# get_it_V4_2.net
KiCad netlist of a schematic drawn in Altium Designer
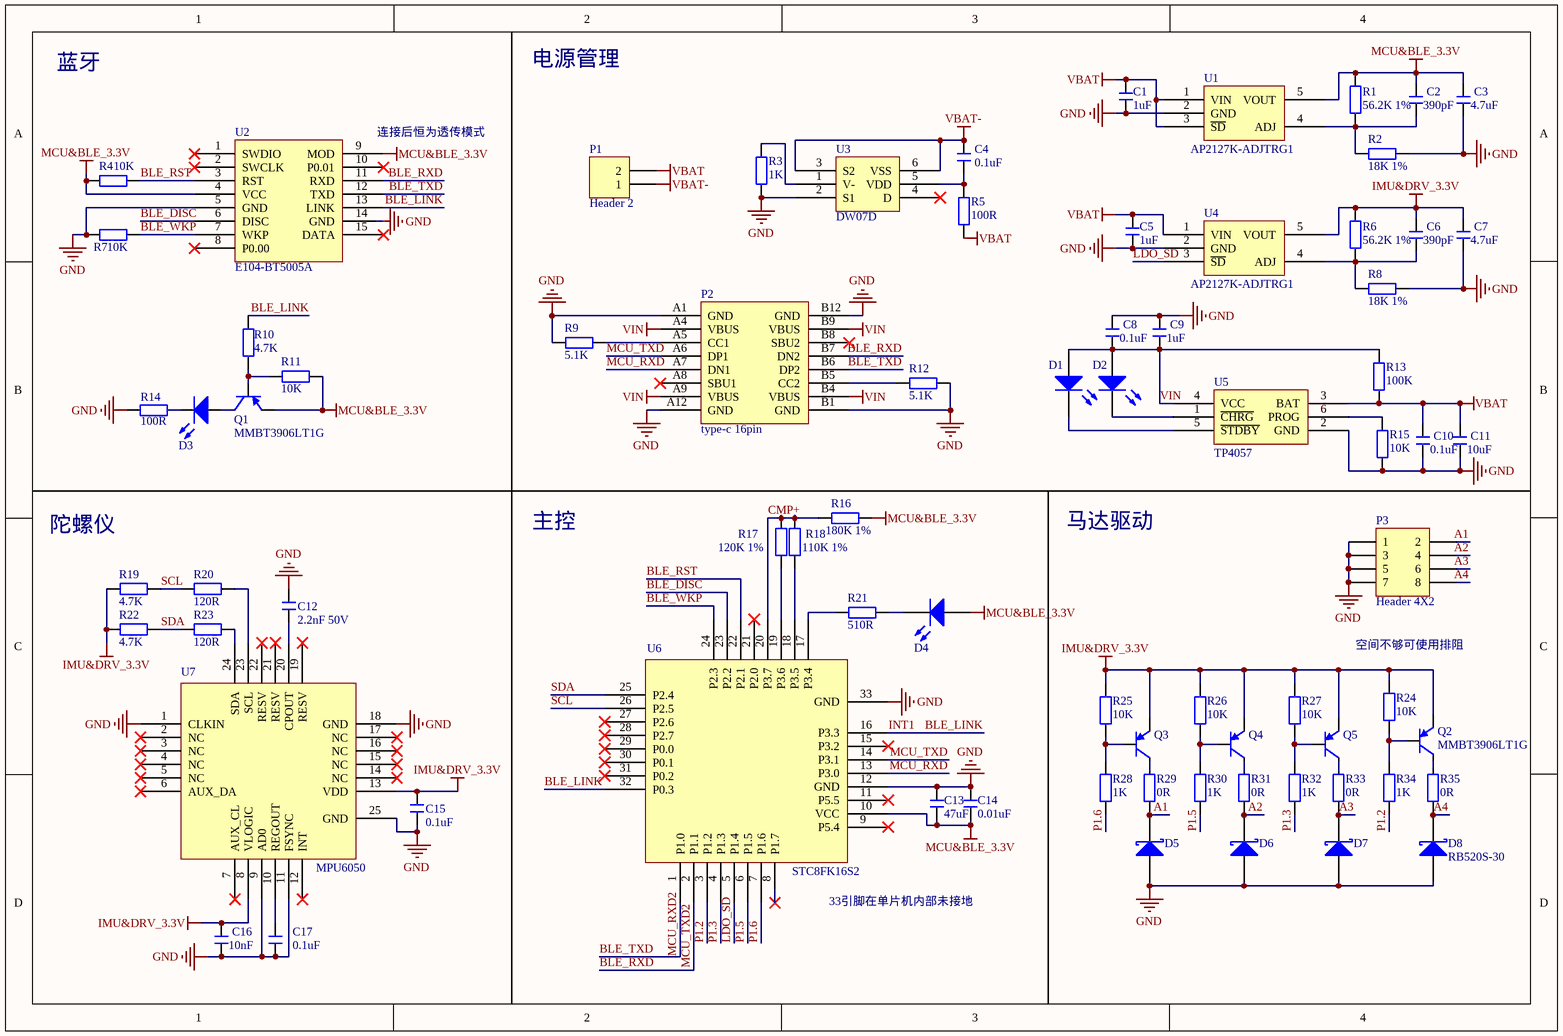
[diagram p0: get it_V4.2.SchDoc]

(export (version "E")
  (design (tool "Eeschema 10.0.6"))
  (components
    (comp (ref "C1")
      (value "1uF")
      (footprint "C 0402_L")
      (description "贴片电容")
      (libsource (lib "altium-import") (part "root_1_C_"))
    )
    (comp (ref "C2")
      (value "390pF")
      (footprint "C 0402_L")
      (description "贴片电容")
      (libsource (lib "altium-import") (part "root_1_C_"))
    )
    (comp (ref "C3")
      (value "4.7uF")
      (footprint "C 0402_L")
      (description "贴片电容")
      (libsource (lib "altium-import") (part "root_1_C_"))
    )
    (comp (ref "C4")
      (value "0.1uF")
      (footprint "C 0402_L")
      (description "贴片电容")
      (libsource (lib "altium-import") (part "root_1_C_"))
    )
    (comp (ref "C5")
      (value "1uF")
      (footprint "C 0402_L")
      (description "贴片电容")
      (libsource (lib "altium-import") (part "root_1_C_"))
    )
    (comp (ref "C6")
      (value "390pF")
      (footprint "C 0402_L")
      (description "贴片电容")
      (libsource (lib "altium-import") (part "root_1_C_"))
    )
    (comp (ref "C7")
      (value "4.7uF")
      (footprint "C 0402_L")
      (description "贴片电容")
      (libsource (lib "altium-import") (part "root_1_C_"))
    )
    (comp (ref "C8")
      (value "0.1uF")
      (footprint "C 0402_L")
      (description "贴片电容")
      (libsource (lib "altium-import") (part "root_1_C_"))
    )
    (comp (ref "C9")
      (value "1uF")
      (footprint "C 0402_L")
      (description "贴片电容")
      (libsource (lib "altium-import") (part "root_1_C_"))
    )
    (comp (ref "C10")
      (value "0.1uF")
      (footprint "C 0402_L")
      (description "贴片电容")
      (libsource (lib "altium-import") (part "root_1_C_"))
    )
    (comp (ref "C11")
      (value "10uF")
      (footprint "C 0402_L")
      (description "贴片电容")
      (libsource (lib "altium-import") (part "root_1_C_"))
    )
    (comp (ref "C12")
      (value "2.2nF 50V")
      (footprint "C 0402_L")
      (description "贴片电容")
      (libsource (lib "altium-import") (part "root_1_C_"))
    )
    (comp (ref "C13")
      (value "47uF")
      (footprint "C 0603_L")
      (description "贴片电容")
      (libsource (lib "altium-import") (part "root_1_C_"))
    )
    (comp (ref "C14")
      (value "0.01uF")
      (footprint "C 0402_L")
      (description "贴片电容")
      (libsource (lib "altium-import") (part "root_1_C_"))
    )
    (comp (ref "C15")
      (value "0.1uF")
      (footprint "C 0402_L")
      (description "贴片电容")
      (libsource (lib "altium-import") (part "root_1_C_"))
    )
    (comp (ref "C16")
      (value "10nF")
      (footprint "C 0402_L")
      (description "贴片电容")
      (libsource (lib "altium-import") (part "root_1_C_"))
    )
    (comp (ref "C17")
      (value "0.1uF")
      (footprint "C 0402_L")
      (description "贴片电容")
      (libsource (lib "altium-import") (part "root_1_C_"))
    )
    (comp (ref "D1")
      (value "LED")
      (footprint "LED_0603")
      (description "发光二极管")
      (libsource (lib "altium-import") (part "root_3_LED_"))
    )
    (comp (ref "D2")
      (value "LED")
      (footprint "LED_0603")
      (description "发光二极管")
      (libsource (lib "altium-import") (part "root_3_LED_"))
    )
    (comp (ref "D3")
      (value "LED")
      (footprint "LED_0603")
      (description "LED GREEN")
      (fields (field (name "PUBLISHER") "Altium Limited"))
      (libsource (lib "Genenal") (part "LED"))
    )
    (comp (ref "D4")
      (value "LED")
      (footprint "LED_0603")
      (description "发光二极管")
      (libsource (lib "altium-import") (part "root_2_LED_"))
    )
    (comp (ref "D5")
      (value "~")
      (footprint "SOD-523")
      (description "肖特基二极管")
      (libsource (lib "altium-import") (part "root_1_SS14_"))
    )
    (comp (ref "D6")
      (value "~")
      (footprint "SOD-523")
      (description "肖特基二极管")
      (libsource (lib "altium-import") (part "root_1_SS14_"))
    )
    (comp (ref "D7")
      (value "~")
      (footprint "SOD-523")
      (description "肖特基二极管")
      (libsource (lib "altium-import") (part "root_1_SS210_"))
    )
    (comp (ref "D8")
      (value "RB520S-30")
      (footprint "SOD-523")
      (description "肖特基二极管")
      (libsource (lib "altium-import") (part "root_1_SS14_"))
    )
    (comp (ref "P1")
      (value "Header 2")
      (footprint "BAT_header")
      (description "Header, 2-Pin")
      (fields (field (name "PUBLISHER") "Altium Limited"))
      (libsource (lib "Miscellaneous Connectors") (part "Header 2"))
    )
    (comp (ref "P2")
      (value "type-c 16pin")
      (footprint "type-c 16pin 沉板母座")
      (libsource (lib "Components") (part "type-c 16pin 沉板母座"))
    )
    (comp (ref "P3")
      (value "Header 4X2")
      (footprint "MOTOR_HEADER")
      (description "Header, 4-Pin, Dual row")
      (fields (field (name "PUBLISHER") "Altium Limited"))
      (libsource (lib "Miscellaneous Connectors") (part "Header 4X2"))
    )
    (comp (ref "Q1")
      (value "MMBT3906LT1G")
      (footprint "SOT23-3L")
      (description "低频放大-PNP型")
      (fields (field (name "版权归属") "封装库来自淘宝 ID：黄晶宝石"))
      (libsource (lib "altium-import") (part "root_3_9012-SMD_"))
    )
    (comp (ref "Q2")
      (value "MMBT3906LT1G")
      (footprint "SOT23-3L")
      (description "低频放大-PNP型")
      (fields (field (name "版权归属") "封装库来自淘宝 ID：黄晶宝石"))
      (libsource (lib "altium-import") (part "root_0_9012-SMD_"))
    )
    (comp (ref "Q3")
      (value "~")
      (footprint "SOT23-3L")
      (description "低频放大-PNP型")
      (fields (field (name "版权归属") "封装库来自淘宝 ID：黄晶宝石"))
      (libsource (lib "altium-import") (part "root_0_9012-SMD_"))
    )
    (comp (ref "Q4")
      (value "~")
      (footprint "SOT23-3L")
      (description "低频放大-PNP型")
      (fields (field (name "版权归属") "封装库来自淘宝 ID：黄晶宝石"))
      (libsource (lib "altium-import") (part "root_0_9012-SMD_"))
    )
    (comp (ref "Q5")
      (value "~")
      (footprint "SOT23-3L")
      (description "低频放大-PNP型")
      (fields (field (name "版权归属") "封装库来自淘宝 ID：黄晶宝石"))
      (libsource (lib "altium-import") (part "root_0_9012-SMD_"))
    )
    (comp (ref "R1")
      (value "56.2K 1%")
      (footprint "R 0402_L")
      (description "贴片电阻")
      (fields (field (name "版权归属") "来自淘宝 ID：黄晶宝石"))
      (libsource (lib "altium-import") (part "root_1_R_"))
    )
    (comp (ref "R2")
      (value "18K 1%")
      (footprint "R 0402_L")
      (description "贴片电阻")
      (fields (field (name "版权归属") "来自淘宝 ID：黄晶宝石"))
      (libsource (lib "altium-import") (part "root_2_R_"))
    )
    (comp (ref "R3")
      (value "1K")
      (footprint "R 0402_L")
      (description "贴片电阻")
      (fields (field (name "版权归属") "来自淘宝 ID：黄晶宝石"))
      (libsource (lib "altium-import") (part "root_1_R_"))
    )
    (comp (ref "R4")
      (value "10K")
      (footprint "R 0402_L")
      (description "贴片电阻")
      (fields (field (name "版权归属") "来自淘宝 ID：黄晶宝石"))
      (libsource (lib "altium-import") (part "root_2_R_"))
    )
    (comp (ref "R5")
      (value "100R")
      (footprint "R 0402_L")
      (description "贴片电阻")
      (fields (field (name "版权归属") "来自淘宝 ID：黄晶宝石"))
      (libsource (lib "altium-import") (part "root_1_R_"))
    )
    (comp (ref "R6")
      (value "56.2K 1%")
      (footprint "R 0402_L")
      (description "贴片电阻")
      (fields (field (name "版权归属") "来自淘宝 ID：黄晶宝石"))
      (libsource (lib "altium-import") (part "root_1_R_"))
    )
    (comp (ref "R7")
      (value "10K")
      (footprint "R 0402_L")
      (description "贴片电阻")
      (fields (field (name "版权归属") "来自淘宝 ID：黄晶宝石"))
      (libsource (lib "altium-import") (part "root_2_R_"))
    )
    (comp (ref "R8")
      (value "18K 1%")
      (footprint "R 0402_L")
      (description "贴片电阻")
      (fields (field (name "版权归属") "来自淘宝 ID：黄晶宝石"))
      (libsource (lib "altium-import") (part "root_2_R_"))
    )
    (comp (ref "R9")
      (value "5.1K")
      (footprint "R 0402_L")
      (description "贴片电阻")
      (fields (field (name "版权归属") "来自淘宝 ID：黄晶宝石"))
      (libsource (lib "0.1 - 电阻-电容-电感") (part "R"))
    )
    (comp (ref "R10")
      (value "4.7K")
      (footprint "R 0402_L")
      (fields (field (name "Comment") "Res") (field (name "PUBLISHER") "Altium Limited"))
      (libsource (lib "") (part "Res_1"))
    )
    (comp (ref "R11")
      (value "10K")
      (footprint "R 0402_L")
      (description "贴片电阻")
      (fields (field (name "版权归属") "来自淘宝 ID：黄晶宝石"))
      (libsource (lib "altium-import") (part "root_2_R_"))
    )
    (comp (ref "R12")
      (value "5.1K")
      (footprint "R 0402_L")
      (description "贴片电阻")
      (fields (field (name "版权归属") "来自淘宝 ID：黄晶宝石"))
      (libsource (lib "0.1 - 电阻-电容-电感") (part "R"))
    )
    (comp (ref "R13")
      (value "100K")
      (footprint "R 0402_L")
      (description "贴片电阻")
      (fields (field (name "版权归属") "来自淘宝 ID：黄晶宝石"))
      (libsource (lib "altium-import") (part "root_1_R_"))
    )
    (comp (ref "R14")
      (value "100R")
      (footprint "R 0402_L")
      (fields (field (name "Comment") "Res") (field (name "PUBLISHER") "Altium Limited"))
      (libsource (lib "Genenal") (part "Res"))
    )
    (comp (ref "R15")
      (value "10K")
      (footprint "R 0402_L")
      (description "贴片电阻")
      (fields (field (name "版权归属") "来自淘宝 ID：黄晶宝石"))
      (libsource (lib "altium-import") (part "root_1_R_"))
    )
    (comp (ref "R16")
      (value "180K 1%")
      (footprint "R 0402_L")
      (description "贴片电阻")
      (fields (field (name "版权归属") "来自淘宝 ID：黄晶宝石"))
      (libsource (lib "altium-import") (part "root_2_R_"))
    )
    (comp (ref "R17")
      (value "120K 1%")
      (footprint "R 0402_L")
      (description "贴片电阻")
      (fields (field (name "版权归属") "来自淘宝 ID：黄晶宝石"))
      (libsource (lib "altium-import") (part "root_3_R_"))
    )
    (comp (ref "R18")
      (value "110K 1%")
      (footprint "R 0402_L")
      (description "贴片电阻")
      (fields (field (name "版权归属") "来自淘宝 ID：黄晶宝石"))
      (libsource (lib "altium-import") (part "root_3_R_"))
    )
    (comp (ref "R19")
      (value "4.7K")
      (footprint "R 0402_L")
      (description "贴片电阻")
      (fields (field (name "版权归属") "来自淘宝 ID：黄晶宝石"))
      (libsource (lib "altium-import") (part "root_0_R_"))
    )
    (comp (ref "R20")
      (value "120R")
      (footprint "R 0402_L")
      (description "贴片电阻")
      (fields (field (name "版权归属") "来自淘宝 ID：黄晶宝石"))
      (libsource (lib "altium-import") (part "root_0_R_"))
    )
    (comp (ref "R21")
      (value "510R")
      (footprint "R 0402_L")
      (description "贴片电阻")
      (fields (field (name "版权归属") "来自淘宝 ID：黄晶宝石"))
      (libsource (lib "altium-import") (part "root_2_R_"))
    )
    (comp (ref "R22")
      (value "4.7K")
      (footprint "R 0402_L")
      (description "贴片电阻")
      (fields (field (name "版权归属") "来自淘宝 ID：黄晶宝石"))
      (libsource (lib "altium-import") (part "root_0_R_"))
    )
    (comp (ref "R23")
      (value "120R")
      (footprint "R 0402_L")
      (description "贴片电阻")
      (fields (field (name "版权归属") "来自淘宝 ID：黄晶宝石"))
      (libsource (lib "altium-import") (part "root_0_R_"))
    )
    (comp (ref "R24")
      (value "10K")
      (footprint "R 0402_L")
      (description "贴片电阻")
      (fields (field (name "版权归属") "来自淘宝 ID：黄晶宝石"))
      (libsource (lib "altium-import") (part "root_1_R_"))
    )
    (comp (ref "R25")
      (value "10K")
      (footprint "R 0402_L")
      (description "贴片电阻")
      (fields (field (name "版权归属") "来自淘宝 ID：黄晶宝石"))
      (libsource (lib "altium-import") (part "root_1_R_"))
    )
    (comp (ref "R26")
      (value "10K")
      (footprint "R 0402_L")
      (description "贴片电阻")
      (fields (field (name "版权归属") "来自淘宝 ID：黄晶宝石"))
      (libsource (lib "altium-import") (part "root_1_R_"))
    )
    (comp (ref "R27")
      (value "10K")
      (footprint "R 0402_L")
      (description "贴片电阻")
      (fields (field (name "版权归属") "来自淘宝 ID：黄晶宝石"))
      (libsource (lib "altium-import") (part "root_1_R_"))
    )
    (comp (ref "R28")
      (value "1K")
      (footprint "R 0402_L")
      (description "贴片电阻")
      (fields (field (name "版权归属") "来自淘宝 ID：黄晶宝石"))
      (libsource (lib "altium-import") (part "root_1_R_"))
    )
    (comp (ref "R29")
      (value "0R")
      (footprint "R 0402_L")
      (description "贴片电阻")
      (fields (field (name "版权归属") "来自淘宝 ID：黄晶宝石"))
      (libsource (lib "altium-import") (part "root_1_R_"))
    )
    (comp (ref "R30")
      (value "1K")
      (footprint "R 0402_L")
      (description "贴片电阻")
      (fields (field (name "版权归属") "来自淘宝 ID：黄晶宝石"))
      (libsource (lib "altium-import") (part "root_1_R_"))
    )
    (comp (ref "R31")
      (value "0R")
      (footprint "R 0402_L")
      (description "贴片电阻")
      (fields (field (name "版权归属") "来自淘宝 ID：黄晶宝石"))
      (libsource (lib "altium-import") (part "root_1_R_"))
    )
    (comp (ref "R32")
      (value "1K")
      (footprint "R 0402_L")
      (description "贴片电阻")
      (fields (field (name "版权归属") "来自淘宝 ID：黄晶宝石"))
      (libsource (lib "altium-import") (part "root_1_R_"))
    )
    (comp (ref "R33")
      (value "0R")
      (footprint "R 0402_L")
      (description "贴片电阻")
      (fields (field (name "版权归属") "来自淘宝 ID：黄晶宝石"))
      (libsource (lib "altium-import") (part "root_1_R_"))
    )
    (comp (ref "R34")
      (value "1K")
      (footprint "R 0402_L")
      (description "贴片电阻")
      (fields (field (name "版权归属") "来自淘宝 ID：黄晶宝石"))
      (libsource (lib "altium-import") (part "root_1_R_"))
    )
    (comp (ref "R35")
      (value "0R")
      (footprint "R 0402_L")
      (description "贴片电阻")
      (fields (field (name "版权归属") "来自淘宝 ID：黄晶宝石"))
      (libsource (lib "altium-import") (part "root_1_R_"))
    )
    (comp (ref "U1")
      (value "AP2127K-ADJTRG1")
      (footprint "SOT-23-5")
      (libsource (lib "Components") (part "AP2127K-ADJTRG1"))
    )
    (comp (ref "U2")
      (value "E104-BT5005A")
      (footprint "E104-BT5005A")
      (libsource (lib "Components") (part "E104-BT5005A"))
    )
    (comp (ref "U3") (value "DW07D") (footprint "SOT-23-6") (libsource (lib "Components") (part "DW06D")))
    (comp (ref "U4")
      (value "AP2127K-ADJTRG1")
      (footprint "SOT-23-5")
      (libsource (lib "Components") (part "AP2127K-ADJTRG1"))
    )
    (comp (ref "U5") (value "TP4057") (footprint "SOT-23-6") (libsource (lib "Components") (part "TP4057")))
    (comp (ref "U6")
      (value "STC8FK16S2")
      (footprint "QFN40P400X400X75_HS-33N")
      (libsource (lib "Components") (part "STC8FK16S2(QFN32)"))
    )
    (comp (ref "U7")
      (value "MPU6050")
      (footprint "QFN50P400X400X90_HS-25N")
      (libsource (lib "Components") (part "MPU6050"))
    )
  )
  (nets
    (net (code "1") (name "/A1") (class "Default")
      (node (ref "D5") (pin "2") (pinfunction "K_2") (pintype "passive"))
      (node (ref "P3") (pin "2") (pinfunction "2_2") (pintype "passive"))
      (node (ref "R29") (pin "1") (pinfunction "1_1") (pintype "passive"))
    )
    (net (code "2") (name "/A2") (class "Default")
      (node (ref "D6") (pin "2") (pinfunction "K_2") (pintype "passive"))
      (node (ref "P3") (pin "4") (pinfunction "4_4") (pintype "passive"))
      (node (ref "R31") (pin "1") (pinfunction "1_1") (pintype "passive"))
    )
    (net (code "3") (name "/A3") (class "Default")
      (node (ref "D7") (pin "2") (pinfunction "K_2") (pintype "passive"))
      (node (ref "P3") (pin "6") (pinfunction "6_6") (pintype "passive"))
      (node (ref "R33") (pin "1") (pinfunction "1_1") (pintype "passive"))
    )
    (net (code "4") (name "/A4") (class "Default")
      (node (ref "D8") (pin "2") (pinfunction "K_2") (pintype "passive"))
      (node (ref "P3") (pin "8") (pinfunction "8_8") (pintype "passive"))
      (node (ref "R35") (pin "1") (pinfunction "1_1") (pintype "passive"))
    )
    (net (code "5") (name "/BLE_DISC") (class "Default")
      (node (ref "U2") (pin "6") (pinfunction "DISC_6") (pintype "passive"))
      (node (ref "U6") (pin "23") (pinfunction "P2.2_23") (pintype "passive"))
    )
    (net (code "6") (name "/BLE_LINK") (class "Default")
      (node (ref "R10") (pin "2") (pinfunction "2_2") (pintype "passive"))
      (node (ref "U2") (pin "13") (pinfunction "LINK_13") (pintype "passive"))
      (node (ref "U6") (pin "16") (pinfunction "P3.3_16") (pintype "passive"))
      (node (ref "U6") (pin "32") (pinfunction "P0.3_32") (pintype "passive"))
    )
    (net (code "7") (name "/BLE_RST") (class "Default")
      (node (ref "R4") (pin "1") (pinfunction "1_1") (pintype "passive"))
      (node (ref "U2") (pin "3") (pinfunction "RST_3") (pintype "passive"))
      (node (ref "U6") (pin "22") (pinfunction "P2.1_22") (pintype "passive"))
    )
    (net (code "8") (name "/BLE_RXD") (class "Default")
      (node (ref "P2") (pin "B7") (pinfunction "DN2_B7") (pintype "passive"))
      (node (ref "U2") (pin "11") (pinfunction "RXD_11") (pintype "passive"))
      (node (ref "U6") (pin "2") (pinfunction "P1.1_2") (pintype "passive"))
    )
    (net (code "9") (name "/BLE_TXD") (class "Default")
      (node (ref "P2") (pin "B6") (pinfunction "DP2_B6") (pintype "passive"))
      (node (ref "U2") (pin "12") (pinfunction "TXD_12") (pintype "passive"))
      (node (ref "U6") (pin "1") (pinfunction "P1.0_1") (pintype "passive"))
    )
    (net (code "10") (name "/BLE_WKP") (class "Default")
      (node (ref "R7") (pin "1") (pinfunction "1_1") (pintype "passive"))
      (node (ref "U2") (pin "7") (pinfunction "WKP_7") (pintype "passive"))
      (node (ref "U6") (pin "24") (pinfunction "P2.3_24") (pintype "passive"))
    )
    (net (code "11") (name "/CMP+") (class "Default")
      (node (ref "R16") (pin "2") (pinfunction "2_2") (pintype "passive"))
      (node (ref "R17") (pin "1") (pinfunction "1_1") (pintype "passive"))
      (node (ref "R18") (pin "1") (pinfunction "1_1") (pintype "passive"))
      (node (ref "U6") (pin "20") (pinfunction "P3.7_20") (pintype "passive"))
    )
    (net (code "12") (name "/LDO_SD") (class "Default")
      (node (ref "U4") (pin "3") (pinfunction "~{SD}_3") (pintype "passive"))
      (node (ref "U6") (pin "5") (pinfunction "P1.4_5") (pintype "passive"))
    )
    (net (code "13") (name "/MCU_RXD") (class "Default")
      (node (ref "P2") (pin "A7") (pinfunction "DN1_A7") (pintype "passive"))
      (node (ref "U6") (pin "13") (pinfunction "P3.0_13") (pintype "passive"))
    )
    (net (code "14") (name "/MCU_TXD") (class "Default")
      (node (ref "P2") (pin "A6") (pinfunction "DP1_A6") (pintype "passive"))
      (node (ref "U6") (pin "14") (pinfunction "P3.1_14") (pintype "passive"))
    )
    (net (code "15") (name "/P1.2") (class "Default")
      (node (ref "R34") (pin "1") (pinfunction "1_1") (pintype "passive"))
      (node (ref "U6") (pin "3") (pinfunction "P1.2_3") (pintype "passive"))
    )
    (net (code "16") (name "/P1.3") (class "Default")
      (node (ref "R32") (pin "1") (pinfunction "1_1") (pintype "passive"))
      (node (ref "U6") (pin "4") (pinfunction "P1.3_4") (pintype "passive"))
    )
    (net (code "17") (name "/P1.5") (class "Default")
      (node (ref "R30") (pin "1") (pinfunction "1_1") (pintype "passive"))
      (node (ref "U6") (pin "6") (pinfunction "P1.5_6") (pintype "passive"))
    )
    (net (code "18") (name "/P1.6") (class "Default")
      (node (ref "R28") (pin "1") (pinfunction "1_1") (pintype "passive"))
      (node (ref "U6") (pin "7") (pinfunction "P1.6_7") (pintype "passive"))
    )
    (net (code "19") (name "/SCL") (class "Default")
      (node (ref "R19") (pin "2") (pinfunction "2_2") (pintype "passive"))
      (node (ref "R20") (pin "1") (pinfunction "1_1") (pintype "passive"))
      (node (ref "U6") (pin "26") (pinfunction "P2.5_26") (pintype "passive"))
    )
    (net (code "20") (name "/SDA") (class "Default")
      (node (ref "R22") (pin "2") (pinfunction "2_2") (pintype "passive"))
      (node (ref "R23") (pin "1") (pinfunction "1_1") (pintype "passive"))
      (node (ref "U6") (pin "25") (pinfunction "P2.4_25") (pintype "passive"))
    )
    (net (code "21") (name "GND") (class "Default")
      (node (ref "C1") (pin "1") (pinfunction "1_1") (pintype "passive"))
      (node (ref "C10") (pin "1") (pinfunction "1_1") (pintype "passive"))
      (node (ref "C11") (pin "1") (pinfunction "1_1") (pintype "passive"))
      (node (ref "C12") (pin "2") (pinfunction "2_2") (pintype "passive"))
      (node (ref "C13") (pin "2") (pinfunction "2_2") (pintype "passive"))
      (node (ref "C14") (pin "2") (pinfunction "2_2") (pintype "passive"))
      (node (ref "C15") (pin "1") (pinfunction "1_1") (pintype "passive"))
      (node (ref "C16") (pin "1") (pinfunction "1_1") (pintype "passive"))
      (node (ref "C17") (pin "1") (pinfunction "1_1") (pintype "passive"))
      (node (ref "C3") (pin "1") (pinfunction "1_1") (pintype "passive"))
      (node (ref "C5") (pin "1") (pinfunction "1_1") (pintype "passive"))
      (node (ref "C7") (pin "1") (pinfunction "1_1") (pintype "passive"))
      (node (ref "C8") (pin "2") (pinfunction "2_2") (pintype "passive"))
      (node (ref "C9") (pin "2") (pinfunction "2_2") (pintype "passive"))
      (node (ref "D5") (pin "1") (pinfunction "A_1") (pintype "passive"))
      (node (ref "D6") (pin "1") (pinfunction "A_1") (pintype "passive"))
      (node (ref "D7") (pin "1") (pinfunction "A_1") (pintype "passive"))
      (node (ref "D8") (pin "1") (pinfunction "A_1") (pintype "passive"))
      (node (ref "P2") (pin "A1") (pinfunction "GND_A1") (pintype "passive"))
      (node (ref "P2") (pin "A12") (pinfunction "GND_A12") (pintype "passive"))
      (node (ref "P2") (pin "B1") (pinfunction "GND_B1") (pintype "passive"))
      (node (ref "P2") (pin "B12") (pinfunction "GND_B12") (pintype "passive"))
      (node (ref "P3") (pin "1") (pinfunction "1_1") (pintype "passive"))
      (node (ref "P3") (pin "3") (pinfunction "3_3") (pintype "passive"))
      (node (ref "P3") (pin "5") (pinfunction "5_5") (pintype "passive"))
      (node (ref "P3") (pin "7") (pinfunction "7_7") (pintype "passive"))
      (node (ref "R12") (pin "2") (pinfunction "2_2") (pintype "passive"))
      (node (ref "R14") (pin "2") (pinfunction "2_2") (pintype "passive"))
      (node (ref "R15") (pin "1") (pinfunction "1_1") (pintype "passive"))
      (node (ref "R2") (pin "1") (pinfunction "1_1") (pintype "passive"))
      (node (ref "R3") (pin "1") (pinfunction "1_1") (pintype "passive"))
      (node (ref "R7") (pin "2") (pinfunction "2_2") (pintype "passive"))
      (node (ref "R8") (pin "1") (pinfunction "1_1") (pintype "passive"))
      (node (ref "R9") (pin "1") (pinfunction "1_1") (pintype "passive"))
      (node (ref "U1") (pin "2") (pinfunction "GND_2") (pintype "passive"))
      (node (ref "U2") (pin "14") (pinfunction "GND_14") (pintype "passive"))
      (node (ref "U2") (pin "5") (pinfunction "GND_5") (pintype "passive"))
      (node (ref "U3") (pin "2") (pinfunction "S1_2") (pintype "passive"))
      (node (ref "U4") (pin "2") (pinfunction "GND_2") (pintype "passive"))
      (node (ref "U5") (pin "2") (pinfunction "GND_2") (pintype "passive"))
      (node (ref "U6") (pin "12") (pinfunction "GND_12") (pintype "passive"))
      (node (ref "U6") (pin "33") (pinfunction "GND_33") (pintype "passive"))
      (node (ref "U7") (pin "1") (pinfunction "CLKIN_1") (pintype "passive"))
      (node (ref "U7") (pin "11") (pinfunction "FSYNC_11") (pintype "passive"))
      (node (ref "U7") (pin "18") (pinfunction "GND_18") (pintype "passive"))
      (node (ref "U7") (pin "25") (pinfunction "GND_25") (pintype "passive"))
      (node (ref "U7") (pin "9") (pinfunction "AD0_9") (pintype "passive"))
    )
    (net (code "22") (name "IMU&DRV_3.3V") (class "Default")
      (node (ref "C15") (pin "2") (pinfunction "2_2") (pintype "passive"))
      (node (ref "C16") (pin "2") (pinfunction "2_2") (pintype "passive"))
      (node (ref "C6") (pin "2") (pinfunction "2_2") (pintype "passive"))
      (node (ref "C7") (pin "2") (pinfunction "2_2") (pintype "passive"))
      (node (ref "Q2") (pin "2") (pinfunction "E_2") (pintype "passive"))
      (node (ref "Q3") (pin "2") (pinfunction "E_2") (pintype "passive"))
      (node (ref "Q4") (pin "2") (pinfunction "E_2") (pintype "passive"))
      (node (ref "Q5") (pin "2") (pinfunction "E_2") (pintype "passive"))
      (node (ref "R19") (pin "1") (pinfunction "1_1") (pintype "passive"))
      (node (ref "R22") (pin "1") (pinfunction "1_1") (pintype "passive"))
      (node (ref "R24") (pin "2") (pinfunction "2_2") (pintype "passive"))
      (node (ref "R25") (pin "2") (pinfunction "2_2") (pintype "passive"))
      (node (ref "R26") (pin "2") (pinfunction "2_2") (pintype "passive"))
      (node (ref "R27") (pin "2") (pinfunction "2_2") (pintype "passive"))
      (node (ref "R6") (pin "2") (pinfunction "2_2") (pintype "passive"))
      (node (ref "U4") (pin "5") (pinfunction "VOUT_5") (pintype "passive"))
      (node (ref "U7") (pin "13") (pinfunction "VDD_13") (pintype "passive"))
      (node (ref "U7") (pin "8") (pinfunction "VLOGIC_8") (pintype "passive"))
    )
    (net (code "23") (name "MCU&BLE_3.3V") (class "Default")
      (node (ref "C13") (pin "1") (pinfunction "1_1") (pintype "passive"))
      (node (ref "C14") (pin "1") (pinfunction "1_1") (pintype "passive"))
      (node (ref "C2") (pin "2") (pinfunction "2_2") (pintype "passive"))
      (node (ref "C3") (pin "2") (pinfunction "2_2") (pintype "passive"))
      (node (ref "D4") (pin "1") (pinfunction "A_1") (pintype "passive"))
      (node (ref "Q1") (pin "2") (pinfunction "E_2") (pintype "passive"))
      (node (ref "R1") (pin "2") (pinfunction "2_2") (pintype "passive"))
      (node (ref "R11") (pin "1") (pinfunction "1_1") (pintype "passive"))
      (node (ref "R16") (pin "1") (pinfunction "1_1") (pintype "passive"))
      (node (ref "R4") (pin "2") (pinfunction "2_2") (pintype "passive"))
      (node (ref "U1") (pin "5") (pinfunction "VOUT_5") (pintype "passive"))
      (node (ref "U2") (pin "4") (pinfunction "VCC_4") (pintype "passive"))
      (node (ref "U2") (pin "9") (pinfunction "MOD_9") (pintype "passive"))
      (node (ref "U6") (pin "10") (pinfunction "VCC_10") (pintype "passive"))
    )
    (net (code "24") (name "Net-(D1-K)") (class "Default")
      (node (ref "D1") (pin "2") (pinfunction "K_2") (pintype "passive"))
      (node (ref "U5") (pin "5") (pinfunction "~{STDBY}_5") (pintype "passive"))
    )
    (net (code "25") (name "Net-(D2-K)") (class "Default")
      (node (ref "D2") (pin "2") (pinfunction "K_2") (pintype "passive"))
      (node (ref "U5") (pin "1") (pinfunction "~{CHRG}_1") (pintype "passive"))
    )
    (net (code "26") (name "Net-(D3-A)") (class "Default")
      (node (ref "D3") (pin "1") (pinfunction "A_1") (pintype "passive"))
      (node (ref "Q1") (pin "3") (pinfunction "C_3") (pintype "passive"))
    )
    (net (code "27") (name "Net-(D3-K)") (class "Default")
      (node (ref "D3") (pin "2") (pinfunction "K_2") (pintype "passive"))
      (node (ref "R14") (pin "1") (pinfunction "1_1") (pintype "passive"))
    )
    (net (code "28") (name "Net-(D4-K)") (class "Default")
      (node (ref "D4") (pin "2") (pinfunction "K_2") (pintype "passive"))
      (node (ref "R21") (pin "1") (pinfunction "1_1") (pintype "passive"))
    )
    (net (code "29") (name "Net-(P2-CC1)") (class "Default")
      (node (ref "P2") (pin "A5") (pinfunction "CC1_A5") (pintype "passive"))
      (node (ref "R9") (pin "2") (pinfunction "2_2") (pintype "passive"))
    )
    (net (code "30") (name "Net-(P2-CC2)") (class "Default")
      (node (ref "P2") (pin "B5") (pinfunction "CC2_B5") (pintype "passive"))
      (node (ref "R12") (pin "1") (pinfunction "1_1") (pintype "passive"))
    )
    (net (code "31") (name "Net-(Q1-B)") (class "Default")
      (node (ref "Q1") (pin "1") (pinfunction "B_1") (pintype "passive"))
      (node (ref "R10") (pin "1") (pinfunction "1_1") (pintype "passive"))
      (node (ref "R11") (pin "2") (pinfunction "2_2") (pintype "passive"))
    )
    (net (code "32") (name "Net-(Q2-B)") (class "Default")
      (node (ref "Q2") (pin "1") (pinfunction "B_1") (pintype "passive"))
      (node (ref "R24") (pin "1") (pinfunction "1_1") (pintype "passive"))
      (node (ref "R34") (pin "2") (pinfunction "2_2") (pintype "passive"))
    )
    (net (code "33") (name "Net-(Q2-C)") (class "Default")
      (node (ref "Q2") (pin "3") (pinfunction "C_3") (pintype "passive"))
      (node (ref "R35") (pin "2") (pinfunction "2_2") (pintype "passive"))
    )
    (net (code "34") (name "Net-(Q3-B)") (class "Default")
      (node (ref "Q3") (pin "1") (pinfunction "B_1") (pintype "passive"))
      (node (ref "R25") (pin "1") (pinfunction "1_1") (pintype "passive"))
      (node (ref "R28") (pin "2") (pinfunction "2_2") (pintype "passive"))
    )
    (net (code "35") (name "Net-(Q3-C)") (class "Default")
      (node (ref "Q3") (pin "3") (pinfunction "C_3") (pintype "passive"))
      (node (ref "R29") (pin "2") (pinfunction "2_2") (pintype "passive"))
    )
    (net (code "36") (name "Net-(Q4-B)") (class "Default")
      (node (ref "Q4") (pin "1") (pinfunction "B_1") (pintype "passive"))
      (node (ref "R26") (pin "1") (pinfunction "1_1") (pintype "passive"))
      (node (ref "R30") (pin "2") (pinfunction "2_2") (pintype "passive"))
    )
    (net (code "37") (name "Net-(Q4-C)") (class "Default")
      (node (ref "Q4") (pin "3") (pinfunction "C_3") (pintype "passive"))
      (node (ref "R31") (pin "2") (pinfunction "2_2") (pintype "passive"))
    )
    (net (code "38") (name "Net-(Q5-B)") (class "Default")
      (node (ref "Q5") (pin "1") (pinfunction "B_1") (pintype "passive"))
      (node (ref "R27") (pin "1") (pinfunction "1_1") (pintype "passive"))
      (node (ref "R32") (pin "2") (pinfunction "2_2") (pintype "passive"))
    )
    (net (code "39") (name "Net-(Q5-C)") (class "Default")
      (node (ref "Q5") (pin "3") (pinfunction "C_3") (pintype "passive"))
      (node (ref "R33") (pin "2") (pinfunction "2_2") (pintype "passive"))
    )
    (net (code "40") (name "Net-(U1-ADJ)") (class "Default")
      (node (ref "C2") (pin "1") (pinfunction "1_1") (pintype "passive"))
      (node (ref "R1") (pin "1") (pinfunction "1_1") (pintype "passive"))
      (node (ref "R2") (pin "2") (pinfunction "2_2") (pintype "passive"))
      (node (ref "U1") (pin "4") (pinfunction "ADJ_4") (pintype "passive"))
    )
    (net (code "41") (name "Net-(U3-V-)") (class "Default")
      (node (ref "R3") (pin "2") (pinfunction "2_2") (pintype "passive"))
      (node (ref "U3") (pin "1") (pinfunction "V-_1") (pintype "passive"))
    )
    (net (code "42") (name "Net-(U3-VDD)") (class "Default")
      (node (ref "C4") (pin "1") (pinfunction "1_1") (pintype "passive"))
      (node (ref "R5") (pin "2") (pinfunction "2_2") (pintype "passive"))
      (node (ref "U3") (pin "5") (pinfunction "VDD_5") (pintype "passive"))
    )
    (net (code "43") (name "Net-(U4-ADJ)") (class "Default")
      (node (ref "C6") (pin "1") (pinfunction "1_1") (pintype "passive"))
      (node (ref "R6") (pin "1") (pinfunction "1_1") (pintype "passive"))
      (node (ref "R8") (pin "2") (pinfunction "2_2") (pintype "passive"))
      (node (ref "U4") (pin "4") (pinfunction "ADJ_4") (pintype "passive"))
    )
    (net (code "44") (name "Net-(U5-PROG)") (class "Default")
      (node (ref "R15") (pin "2") (pinfunction "2_2") (pintype "passive"))
      (node (ref "U5") (pin "6") (pinfunction "PROG_6") (pintype "passive"))
    )
    (net (code "45") (name "Net-(U6-P3.4)") (class "Default")
      (node (ref "R21") (pin "2") (pinfunction "2_2") (pintype "passive"))
      (node (ref "U6") (pin "17") (pinfunction "P3.4_17") (pintype "passive"))
    )
    (net (code "46") (name "Net-(U6-P3.5)") (class "Default")
      (node (ref "R18") (pin "2") (pinfunction "2_2") (pintype "passive"))
      (node (ref "U6") (pin "18") (pinfunction "P3.5_18") (pintype "passive"))
    )
    (net (code "47") (name "Net-(U6-P3.6)") (class "Default")
      (node (ref "R17") (pin "2") (pinfunction "2_2") (pintype "passive"))
      (node (ref "U6") (pin "19") (pinfunction "P3.6_19") (pintype "passive"))
    )
    (net (code "48") (name "Net-(U7-CPOUT)") (class "Default")
      (node (ref "C12") (pin "1") (pinfunction "1_1") (pintype "passive"))
      (node (ref "U7") (pin "20") (pinfunction "CPOUT_20") (pintype "passive"))
    )
    (net (code "49") (name "Net-(U7-REGOUT)") (class "Default")
      (node (ref "C17") (pin "2") (pinfunction "2_2") (pintype "passive"))
      (node (ref "U7") (pin "10") (pinfunction "REGOUT_10") (pintype "passive"))
    )
    (net (code "50") (name "Net-(U7-SCL)") (class "Default")
      (node (ref "R20") (pin "2") (pinfunction "2_2") (pintype "passive"))
      (node (ref "U7") (pin "23") (pinfunction "SCL_23") (pintype "passive"))
    )
    (net (code "51") (name "Net-(U7-SDA)") (class "Default")
      (node (ref "R23") (pin "2") (pinfunction "2_2") (pintype "passive"))
      (node (ref "U7") (pin "24") (pinfunction "SDA_24") (pintype "passive"))
    )
    (net (code "52") (name "VBAT") (class "Default")
      (node (ref "C1") (pin "2") (pinfunction "2_2") (pintype "passive"))
      (node (ref "C10") (pin "2") (pinfunction "2_2") (pintype "passive"))
      (node (ref "C11") (pin "2") (pinfunction "2_2") (pintype "passive"))
      (node (ref "C5") (pin "2") (pinfunction "2_2") (pintype "passive"))
      (node (ref "P1") (pin "2") (pinfunction "2_2") (pintype "passive"))
      (node (ref "R13") (pin "1") (pinfunction "1_1") (pintype "passive"))
      (node (ref "R5") (pin "1") (pinfunction "1_1") (pintype "passive"))
      (node (ref "U1") (pin "1") (pinfunction "VIN_1") (pintype "passive"))
      (node (ref "U1") (pin "3") (pinfunction "~{SD}_3") (pintype "passive"))
      (node (ref "U4") (pin "1") (pinfunction "VIN_1") (pintype "passive"))
      (node (ref "U5") (pin "3") (pinfunction "BAT_3") (pintype "passive"))
    )
    (net (code "53") (name "VBAT-") (class "Default")
      (node (ref "C4") (pin "2") (pinfunction "2_2") (pintype "passive"))
      (node (ref "P1") (pin "1") (pinfunction "1_1") (pintype "passive"))
      (node (ref "U3") (pin "3") (pinfunction "S2_3") (pintype "passive"))
      (node (ref "U3") (pin "6") (pinfunction "VSS_6") (pintype "passive"))
    )
    (net (code "54") (name "VIN") (class "Default")
      (node (ref "C8") (pin "1") (pinfunction "1_1") (pintype "passive"))
      (node (ref "C9") (pin "1") (pinfunction "1_1") (pintype "passive"))
      (node (ref "D1") (pin "1") (pinfunction "A_1") (pintype "passive"))
      (node (ref "D2") (pin "1") (pinfunction "A_1") (pintype "passive"))
      (node (ref "P2") (pin "A4") (pinfunction "VBUS_A4") (pintype "passive"))
      (node (ref "P2") (pin "A9") (pinfunction "VBUS_A9") (pintype "passive"))
      (node (ref "P2") (pin "B4") (pinfunction "VBUS_B4") (pintype "passive"))
      (node (ref "P2") (pin "B9") (pinfunction "VBUS_B9") (pintype "passive"))
      (node (ref "R13") (pin "2") (pinfunction "2_2") (pintype "passive"))
      (node (ref "U5") (pin "4") (pinfunction "VCC_4") (pintype "passive"))
    )
    (net (code "55") (name "unconnected-(P2-SBU1-PadA8)") (class "Default")
      (node (ref "P2") (pin "A8") (pinfunction "SBU1_A8") (pintype "passive+no_connect"))
    )
    (net (code "56") (name "unconnected-(P2-SBU2-PadB8)") (class "Default")
      (node (ref "P2") (pin "B8") (pinfunction "SBU2_B8") (pintype "passive+no_connect"))
    )
    (net (code "57") (name "unconnected-(U2-DATA-Pad15)") (class "Default")
      (node (ref "U2") (pin "15") (pinfunction "DATA_15") (pintype "passive+no_connect"))
    )
    (net (code "58") (name "unconnected-(U2-P0.00-Pad8)") (class "Default")
      (node (ref "U2") (pin "8") (pinfunction "P0.00_8") (pintype "passive+no_connect"))
    )
    (net (code "59") (name "unconnected-(U2-P0.01-Pad10)") (class "Default")
      (node (ref "U2") (pin "10") (pinfunction "P0.01_10") (pintype "passive+no_connect"))
    )
    (net (code "60") (name "unconnected-(U2-SWCLK-Pad2)") (class "Default")
      (node (ref "U2") (pin "2") (pinfunction "SWCLK_2") (pintype "passive+no_connect"))
    )
    (net (code "61") (name "unconnected-(U2-SWDIO-Pad1)") (class "Default")
      (node (ref "U2") (pin "1") (pinfunction "SWDIO_1") (pintype "passive+no_connect"))
    )
    (net (code "62") (name "unconnected-(U3-D-Pad4)") (class "Default")
      (node (ref "U3") (pin "4") (pinfunction "D_4") (pintype "passive+no_connect"))
    )
    (net (code "63") (name "unconnected-(U6-P0.0-Pad29)") (class "Default")
      (node (ref "U6") (pin "29") (pinfunction "P0.0_29") (pintype "passive+no_connect"))
    )
    (net (code "64") (name "unconnected-(U6-P0.1-Pad30)") (class "Default")
      (node (ref "U6") (pin "30") (pinfunction "P0.1_30") (pintype "passive+no_connect"))
    )
    (net (code "65") (name "unconnected-(U6-P0.2-Pad31)") (class "Default")
      (node (ref "U6") (pin "31") (pinfunction "P0.2_31") (pintype "passive+no_connect"))
    )
    (net (code "66") (name "unconnected-(U6-P1.7-Pad8)") (class "Default")
      (node (ref "U6") (pin "8") (pinfunction "P1.7_8") (pintype "passive+no_connect"))
    )
    (net (code "67") (name "unconnected-(U6-P2.0-Pad21)") (class "Default")
      (node (ref "U6") (pin "21") (pinfunction "P2.0_21") (pintype "passive+no_connect"))
    )
    (net (code "68") (name "unconnected-(U6-P2.6-Pad27)") (class "Default")
      (node (ref "U6") (pin "27") (pinfunction "P2.6_27") (pintype "passive+no_connect"))
    )
    (net (code "69") (name "unconnected-(U6-P2.7-Pad28)") (class "Default")
      (node (ref "U6") (pin "28") (pinfunction "P2.7_28") (pintype "passive+no_connect"))
    )
    (net (code "70") (name "unconnected-(U6-P3.2-Pad15)") (class "Default")
      (node (ref "U6") (pin "15") (pinfunction "P3.2_15") (pintype "passive+no_connect"))
    )
    (net (code "71") (name "unconnected-(U6-P5.4-Pad9)") (class "Default")
      (node (ref "U6") (pin "9") (pinfunction "P5.4_9") (pintype "passive+no_connect"))
    )
    (net (code "72") (name "unconnected-(U6-P5.5-Pad11)") (class "Default")
      (node (ref "U6") (pin "11") (pinfunction "P5.5_11") (pintype "passive+no_connect"))
    )
    (net (code "73") (name "unconnected-(U7-AUX_CL-Pad7)") (class "Default")
      (node (ref "U7") (pin "7") (pinfunction "AUX_CL_7") (pintype "passive+no_connect"))
    )
    (net (code "74") (name "unconnected-(U7-AUX_DA-Pad6)") (class "Default")
      (node (ref "U7") (pin "6") (pinfunction "AUX_DA_6") (pintype "passive+no_connect"))
    )
    (net (code "75") (name "unconnected-(U7-INT-Pad12)") (class "Default")
      (node (ref "U7") (pin "12") (pinfunction "INT_12") (pintype "passive+no_connect"))
    )
    (net (code "76") (name "unconnected-(U7-NC-Pad2)") (class "Default")
      (node (ref "U7") (pin "2") (pinfunction "NC_2") (pintype "passive+no_connect"))
    )
    (net (code "77") (name "unconnected-(U7-NC-Pad3)") (class "Default")
      (node (ref "U7") (pin "3") (pinfunction "NC_3") (pintype "passive+no_connect"))
    )
    (net (code "78") (name "unconnected-(U7-NC-Pad4)") (class "Default")
      (node (ref "U7") (pin "4") (pinfunction "NC_4") (pintype "passive+no_connect"))
    )
    (net (code "79") (name "unconnected-(U7-NC-Pad5)") (class "Default")
      (node (ref "U7") (pin "5") (pinfunction "NC_5") (pintype "passive+no_connect"))
    )
    (net (code "80") (name "unconnected-(U7-NC-Pad14)") (class "Default")
      (node (ref "U7") (pin "14") (pinfunction "NC_14") (pintype "passive+no_connect"))
    )
    (net (code "81") (name "unconnected-(U7-NC-Pad15)") (class "Default")
      (node (ref "U7") (pin "15") (pinfunction "NC_15") (pintype "passive+no_connect"))
    )
    (net (code "82") (name "unconnected-(U7-NC-Pad16)") (class "Default")
      (node (ref "U7") (pin "16") (pinfunction "NC_16") (pintype "passive+no_connect"))
    )
    (net (code "83") (name "unconnected-(U7-NC-Pad17)") (class "Default")
      (node (ref "U7") (pin "17") (pinfunction "NC_17") (pintype "passive+no_connect"))
    )
    (net (code "84") (name "unconnected-(U7-RESV-Pad19)") (class "Default")
      (node (ref "U7") (pin "19") (pinfunction "RESV_19") (pintype "passive+no_connect"))
    )
    (net (code "85") (name "unconnected-(U7-RESV-Pad21)") (class "Default")
      (node (ref "U7") (pin "21") (pinfunction "RESV_21") (pintype "passive+no_connect"))
    )
    (net (code "86") (name "unconnected-(U7-RESV-Pad22)") (class "Default")
      (node (ref "U7") (pin "22") (pinfunction "RESV_22") (pintype "passive+no_connect"))
    )
  )
)
